# LambdaWide.net
KiCad netlist of a schematic drawn in Altium Designer
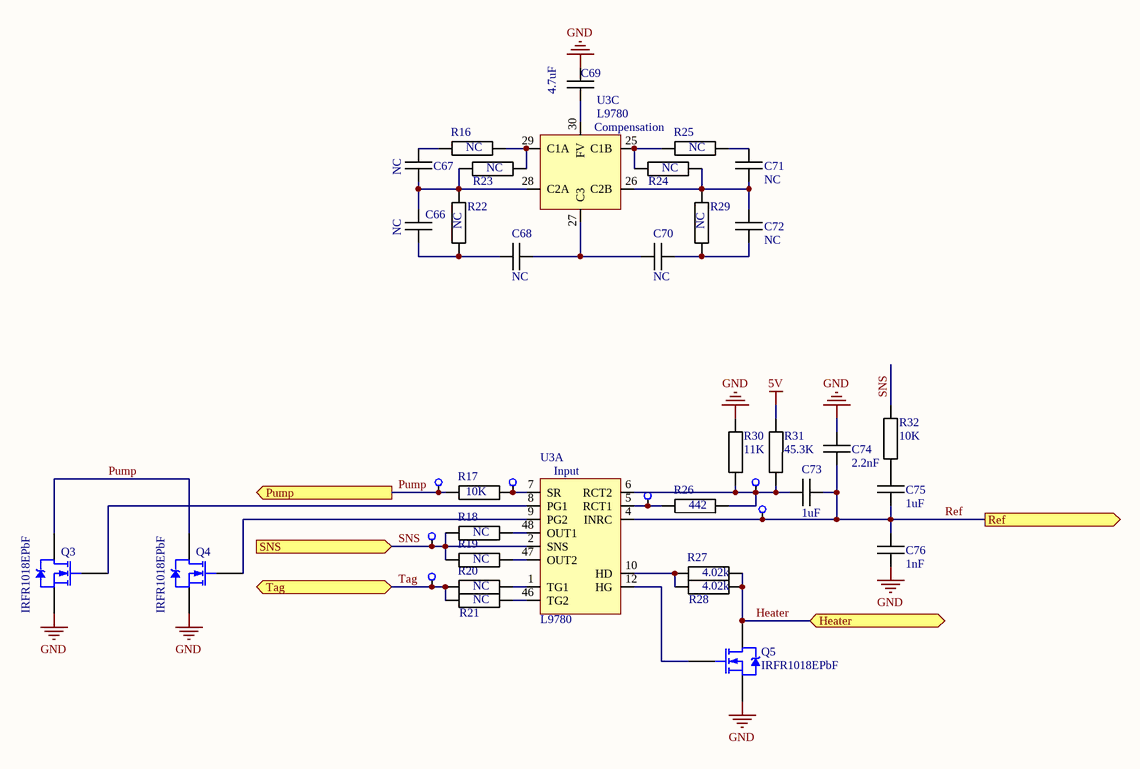
[diagram p0: LambdaWide.SchDoc]

(export (version "E")
  (design (tool "Eeschema 10.0.6"))
  (components
    (comp (ref "C66") (value "NC") (footprint "SMD 0603") (libsource (lib "Maks_lib") (part "Capasitor")))
    (comp (ref "C67") (value "NC") (footprint "SMD 0603") (libsource (lib "Maks_lib") (part "Capasitor")))
    (comp (ref "C68") (value "NC") (footprint "SMD 0603") (libsource (lib "Maks_lib") (part "Capasitor")))
    (comp (ref "C69")
      (value "4.7uF")
      (footprint "SMD 0603")
      (description "CC0603KRX5R6BB475")
      (libsource (lib "Maks_lib") (part "Capasitor"))
    )
    (comp (ref "C70") (value "NC") (footprint "SMD 0603") (libsource (lib "Maks_lib") (part "Capasitor")))
    (comp (ref "C71") (value "NC") (footprint "SMD 0603") (libsource (lib "Maks_lib") (part "Capasitor")))
    (comp (ref "C72") (value "NC") (footprint "SMD 0603") (libsource (lib "Maks_lib") (part "Capasitor")))
    (comp (ref "C73")
      (value "1uF")
      (footprint "SMD 0603")
      (description "CL10A105KB8NNNC")
      (libsource (lib "Maks_lib") (part "Capasitor"))
    )
    (comp (ref "C74")
      (value "2.2nF")
      (footprint "SMD 0603")
      (description "CC0603KRX7R9BB222")
      (libsource (lib "Maks_lib") (part "Capasitor"))
    )
    (comp (ref "C75")
      (value "1uF")
      (footprint "SMD 0603")
      (description "CL10A105KB8NNNC")
      (libsource (lib "Maks_lib") (part "Capasitor"))
    )
    (comp (ref "C76")
      (value "1nF")
      (footprint "SMD 0603")
      (description "CC0603KRX7R9BB102")
      (libsource (lib "Maks_lib") (part "Capasitor"))
    )
    (comp (ref "Q3")
      (value "IRFR1018EPbF")
      (footprint "DPAK228P991X238-3M")
      (description "HEXFET Power MOSFET")
      (libsource (lib "Maks_lib") (part "IRFR1018EPbF"))
    )
    (comp (ref "Q4")
      (value "IRFR1018EPbF")
      (footprint "DPAK228P991X238-3M")
      (description "HEXFET Power MOSFET")
      (libsource (lib "Maks_lib") (part "IRFR1018EPbF"))
    )
    (comp (ref "Q5")
      (value "IRFR1018EPbF")
      (footprint "DPAK228P991X238-3M")
      (description "HEXFET Power MOSFET")
      (libsource (lib "Maks_lib") (part "IRFR1018EPbF"))
    )
    (comp (ref "R16") (value "NC") (footprint "SMD 0603") (libsource (lib "Maks_lib") (part "Resistor")))
    (comp (ref "R17")
      (value "10K")
      (footprint "SMD 0603")
      (description "RC0603FR-0710KL")
      (libsource (lib "") (part "Resistor_1"))
    )
    (comp (ref "R18") (value "NC") (footprint "SMD 0603") (libsource (lib "Maks_lib") (part "Resistor")))
    (comp (ref "R19") (value "NC") (footprint "SMD 0603") (libsource (lib "Maks_lib") (part "Resistor")))
    (comp (ref "R20") (value "NC") (footprint "SMD 0603") (libsource (lib "Maks_lib") (part "Resistor")))
    (comp (ref "R21") (value "NC") (footprint "SMD 0603") (libsource (lib "Maks_lib") (part "Resistor")))
    (comp (ref "R22") (value "NC") (footprint "SMD 0603") (libsource (lib "Maks_lib") (part "Resistor")))
    (comp (ref "R23") (value "NC") (footprint "SMD 0603") (libsource (lib "Maks_lib") (part "Resistor")))
    (comp (ref "R24") (value "NC") (footprint "SMD 0603") (libsource (lib "Maks_lib") (part "Resistor")))
    (comp (ref "R25") (value "NC") (footprint "SMD 0603") (libsource (lib "Maks_lib") (part "Resistor")))
    (comp (ref "R26")
      (value "442")
      (footprint "SMD 0603")
      (description "RC0603FR-07442RL")
      (libsource (lib "") (part "Resistor_1"))
    )
    (comp (ref "R27")
      (value "4.02k")
      (footprint "SMD 0603")
      (description "RC0603FR-074K02L")
      (libsource (lib "Maks_lib") (part "Resistor"))
    )
    (comp (ref "R28")
      (value "4.02k")
      (footprint "SMD 0603")
      (description "RC0603FR-074K02L")
      (libsource (lib "Maks_lib") (part "Resistor"))
    )
    (comp (ref "R29") (value "NC") (footprint "SMD 0603") (libsource (lib "Maks_lib") (part "Resistor")))
    (comp (ref "R30")
      (value "11K")
      (footprint "SMD 0603")
      (description "RC0603FR-0711KL")
      (libsource (lib "") (part "Resistor_1"))
    )
    (comp (ref "R31")
      (value "45.3K")
      (footprint "SMD 0603")
      (description "RC0603FR-0745K3L")
      (libsource (lib "") (part "Resistor_1"))
    )
    (comp (ref "R32")
      (value "10K")
      (footprint "SMD 0603")
      (description "RC0603FR-0710KL")
      (libsource (lib "") (part "Resistor_1"))
    )
    (comp (ref "TP43")
      (value "TestPoint")
      (footprint "TESTPOINT")
      (description "testPoint")
      (libsource (lib "Maks_lib") (part "TestPoint"))
    )
    (comp (ref "TP44")
      (value "TestPoint")
      (footprint "TESTPOINT")
      (description "testPoint")
      (libsource (lib "Maks_lib") (part "TestPoint"))
    )
    (comp (ref "TP45")
      (value "TestPoint")
      (footprint "TESTPOINT")
      (description "testPoint")
      (libsource (lib "Maks_lib") (part "TestPoint"))
    )
    (comp (ref "TP46")
      (value "TestPoint")
      (footprint "TESTPOINT")
      (description "testPoint")
      (libsource (lib "Maks_lib") (part "TestPoint"))
    )
    (comp (ref "TP47")
      (value "TestPoint")
      (footprint "TESTPOINT")
      (description "testPoint")
      (libsource (lib "Maks_lib") (part "TestPoint"))
    )
    (comp (ref "TP48")
      (value "TestPoint")
      (footprint "TESTPOINT")
      (description "testPoint")
      (libsource (lib "Maks_lib") (part "TestPoint"))
    )
    (comp (ref "TP49")
      (value "TestPoint")
      (footprint "TESTPOINT")
      (description "testPoint")
      (libsource (lib "Maks_lib") (part "TestPoint"))
    )
    (comp (ref "U3")
      (value "L9780")
      (footprint "LQFP-48N")
      (description "Wide range air fuel sensor control interface")
      (libsource (lib "Maks_lib") (part "L9780"))
    )
  )
  (nets
    (net (code "1") (name "/Heater") (class "Default")
      (node (ref "Q5") (pin "4") (pinfunction "D_4") (pintype "passive"))
      (node (ref "R27") (pin "1") (pinfunction "1_1") (pintype "passive"))
      (node (ref "R28") (pin "1") (pinfunction "1_1") (pintype "passive"))
    )
    (net (code "2") (name "/Pump") (class "Default")
      (node (ref "Q3") (pin "4") (pinfunction "D_4") (pintype "passive"))
      (node (ref "Q4") (pin "4") (pinfunction "D_4") (pintype "passive"))
      (node (ref "R17") (pin "2") (pinfunction "2_2") (pintype "passive"))
      (node (ref "TP45") (pin "0") (pinfunction "0_0") (pintype "passive"))
    )
    (net (code "3") (name "/Ref") (class "Default")
      (node (ref "C73") (pin "2") (pinfunction "2_2") (pintype "passive"))
      (node (ref "C74") (pin "1") (pinfunction "1_1") (pintype "passive"))
      (node (ref "C75") (pin "2") (pinfunction "2_2") (pintype "passive"))
      (node (ref "C76") (pin "2") (pinfunction "2_2") (pintype "passive"))
      (node (ref "TP49") (pin "0") (pinfunction "0_0") (pintype "passive"))
      (node (ref "U3") (pin "4") (pinfunction "INRC_4") (pintype "passive"))
    )
    (net (code "4") (name "/SNS") (class "Default")
      (node (ref "R18") (pin "2") (pinfunction "2_2") (pintype "passive"))
      (node (ref "R19") (pin "2") (pinfunction "2_2") (pintype "passive"))
      (node (ref "R32") (pin "2") (pinfunction "2_2") (pintype "passive"))
      (node (ref "TP43") (pin "0") (pinfunction "0_0") (pintype "passive"))
      (node (ref "U3") (pin "2") (pinfunction "SNS_2") (pintype "passive"))
    )
    (net (code "5") (name "/Tag") (class "Default")
      (node (ref "R20") (pin "2") (pinfunction "2_2") (pintype "passive"))
      (node (ref "R21") (pin "2") (pinfunction "2_2") (pintype "passive"))
      (node (ref "TP44") (pin "0") (pinfunction "0_0") (pintype "passive"))
    )
    (net (code "6") (name "5V") (class "Default")
      (node (ref "R31") (pin "2") (pinfunction "2_2") (pintype "passive"))
    )
    (net (code "7") (name "GND") (class "Default")
      (node (ref "C69") (pin "2") (pinfunction "2_2") (pintype "passive"))
      (node (ref "C74") (pin "2") (pinfunction "2_2") (pintype "passive"))
      (node (ref "C76") (pin "1") (pinfunction "1_1") (pintype "passive"))
      (node (ref "Q3") (pin "3") (pinfunction "S_3") (pintype "passive"))
      (node (ref "Q4") (pin "3") (pinfunction "S_3") (pintype "passive"))
      (node (ref "Q5") (pin "3") (pinfunction "S_3") (pintype "passive"))
      (node (ref "R30") (pin "1") (pinfunction "1_1") (pintype "passive"))
    )
    (net (code "8") (name "Net-(C66-Pad2)") (class "Default")
      (node (ref "C66") (pin "2") (pinfunction "2_2") (pintype "passive"))
      (node (ref "C68") (pin "2") (pinfunction "2_2") (pintype "passive"))
      (node (ref "R22") (pin "2") (pinfunction "2_2") (pintype "passive"))
    )
    (net (code "9") (name "Net-(C67-Pad1)") (class "Default")
      (node (ref "C67") (pin "1") (pinfunction "1_1") (pintype "passive"))
      (node (ref "R16") (pin "1") (pinfunction "1_1") (pintype "passive"))
    )
    (net (code "10") (name "Net-(C70-Pad1)") (class "Default")
      (node (ref "C70") (pin "1") (pinfunction "1_1") (pintype "passive"))
      (node (ref "C72") (pin "2") (pinfunction "2_2") (pintype "passive"))
      (node (ref "R29") (pin "2") (pinfunction "2_2") (pintype "passive"))
    )
    (net (code "11") (name "Net-(C71-Pad1)") (class "Default")
      (node (ref "C71") (pin "1") (pinfunction "1_1") (pintype "passive"))
      (node (ref "R25") (pin "1") (pinfunction "1_1") (pintype "passive"))
    )
    (net (code "12") (name "Net-(C75-Pad1)") (class "Default")
      (node (ref "C75") (pin "1") (pinfunction "1_1") (pintype "passive"))
      (node (ref "R32") (pin "1") (pinfunction "1_1") (pintype "passive"))
    )
    (net (code "13") (name "Net-(Q3-G)") (class "Default")
      (node (ref "Q3") (pin "1") (pinfunction "G_1") (pintype "passive"))
      (node (ref "U3") (pin "8") (pinfunction "PG1_8") (pintype "passive"))
    )
    (net (code "14") (name "Net-(Q4-G)") (class "Default")
      (node (ref "Q4") (pin "1") (pinfunction "G_1") (pintype "passive"))
      (node (ref "U3") (pin "9") (pinfunction "PG2_9") (pintype "passive"))
    )
    (net (code "15") (name "Net-(Q5-G)") (class "Default")
      (node (ref "Q5") (pin "1") (pinfunction "G_1") (pintype "passive"))
      (node (ref "U3") (pin "12") (pinfunction "HG_12") (pintype "passive"))
    )
    (net (code "16") (name "Net-(U3A-HD)") (class "Default")
      (node (ref "R27") (pin "2") (pinfunction "2_2") (pintype "passive"))
      (node (ref "R28") (pin "2") (pinfunction "2_2") (pintype "passive"))
      (node (ref "U3") (pin "10") (pinfunction "HD_10") (pintype "passive"))
    )
    (net (code "17") (name "Net-(U3A-OUT1)") (class "Default")
      (node (ref "R18") (pin "1") (pinfunction "1_1") (pintype "passive"))
      (node (ref "U3") (pin "48") (pinfunction "OUT1_48") (pintype "passive"))
    )
    (net (code "18") (name "Net-(U3A-OUT2)") (class "Default")
      (node (ref "R19") (pin "1") (pinfunction "1_1") (pintype "passive"))
      (node (ref "U3") (pin "47") (pinfunction "OUT2_47") (pintype "passive"))
    )
    (net (code "19") (name "Net-(U3A-RCT1)") (class "Default")
      (node (ref "R26") (pin "1") (pinfunction "1_1") (pintype "passive"))
      (node (ref "TP47") (pin "0") (pinfunction "0_0") (pintype "passive"))
      (node (ref "U3") (pin "5") (pinfunction "RCT1_5") (pintype "passive"))
    )
    (net (code "20") (name "Net-(U3A-RCT2)") (class "Default")
      (node (ref "C73") (pin "1") (pinfunction "1_1") (pintype "passive"))
      (node (ref "R26") (pin "2") (pinfunction "2_2") (pintype "passive"))
      (node (ref "R30") (pin "2") (pinfunction "2_2") (pintype "passive"))
      (node (ref "R31") (pin "1") (pinfunction "1_1") (pintype "passive"))
      (node (ref "TP48") (pin "0") (pinfunction "0_0") (pintype "passive"))
      (node (ref "U3") (pin "6") (pinfunction "RCT2_6") (pintype "passive"))
    )
    (net (code "21") (name "Net-(U3A-SR)") (class "Default")
      (node (ref "R17") (pin "1") (pinfunction "1_1") (pintype "passive"))
      (node (ref "TP46") (pin "0") (pinfunction "0_0") (pintype "passive"))
      (node (ref "U3") (pin "7") (pinfunction "SR_7") (pintype "passive"))
    )
    (net (code "22") (name "Net-(U3A-TG1)") (class "Default")
      (node (ref "R20") (pin "1") (pinfunction "1_1") (pintype "passive"))
      (node (ref "U3") (pin "1") (pinfunction "TG1_1") (pintype "passive"))
    )
    (net (code "23") (name "Net-(U3A-TG2)") (class "Default")
      (node (ref "R21") (pin "1") (pinfunction "1_1") (pintype "passive"))
      (node (ref "U3") (pin "46") (pinfunction "TG2_46") (pintype "passive"))
    )
    (net (code "24") (name "Net-(U3C-C1A)") (class "Default")
      (node (ref "R16") (pin "2") (pinfunction "2_2") (pintype "passive"))
      (node (ref "R23") (pin "2") (pinfunction "2_2") (pintype "passive"))
      (node (ref "U3") (pin "29") (pinfunction "C1A_29") (pintype "passive"))
    )
    (net (code "25") (name "Net-(U3C-C1B)") (class "Default")
      (node (ref "R24") (pin "2") (pinfunction "2_2") (pintype "passive"))
      (node (ref "R25") (pin "2") (pinfunction "2_2") (pintype "passive"))
      (node (ref "U3") (pin "25") (pinfunction "C1B_25") (pintype "passive"))
    )
    (net (code "26") (name "Net-(U3C-C2A)") (class "Default")
      (node (ref "C66") (pin "1") (pinfunction "1_1") (pintype "passive"))
      (node (ref "C67") (pin "2") (pinfunction "2_2") (pintype "passive"))
      (node (ref "R22") (pin "1") (pinfunction "1_1") (pintype "passive"))
      (node (ref "R23") (pin "1") (pinfunction "1_1") (pintype "passive"))
      (node (ref "U3") (pin "28") (pinfunction "C2A_28") (pintype "passive"))
    )
    (net (code "27") (name "Net-(U3C-C2B)") (class "Default")
      (node (ref "C71") (pin "2") (pinfunction "2_2") (pintype "passive"))
      (node (ref "C72") (pin "1") (pinfunction "1_1") (pintype "passive"))
      (node (ref "R24") (pin "1") (pinfunction "1_1") (pintype "passive"))
      (node (ref "R29") (pin "1") (pinfunction "1_1") (pintype "passive"))
      (node (ref "U3") (pin "26") (pinfunction "C2B_26") (pintype "passive"))
    )
    (net (code "28") (name "Net-(U3C-C3)") (class "Default")
      (node (ref "C68") (pin "1") (pinfunction "1_1") (pintype "passive"))
      (node (ref "C70") (pin "2") (pinfunction "2_2") (pintype "passive"))
      (node (ref "U3") (pin "27") (pinfunction "C3_27") (pintype "passive"))
    )
    (net (code "29") (name "Net-(U3C-FV)") (class "Default")
      (node (ref "C69") (pin "1") (pinfunction "1_1") (pintype "passive"))
      (node (ref "U3") (pin "30") (pinfunction "FV_30") (pintype "passive"))
    )
  )
)
